# ESC-simple_V2A_ervinedit.net
KiCad netlist of a schematic drawn in EAGLE
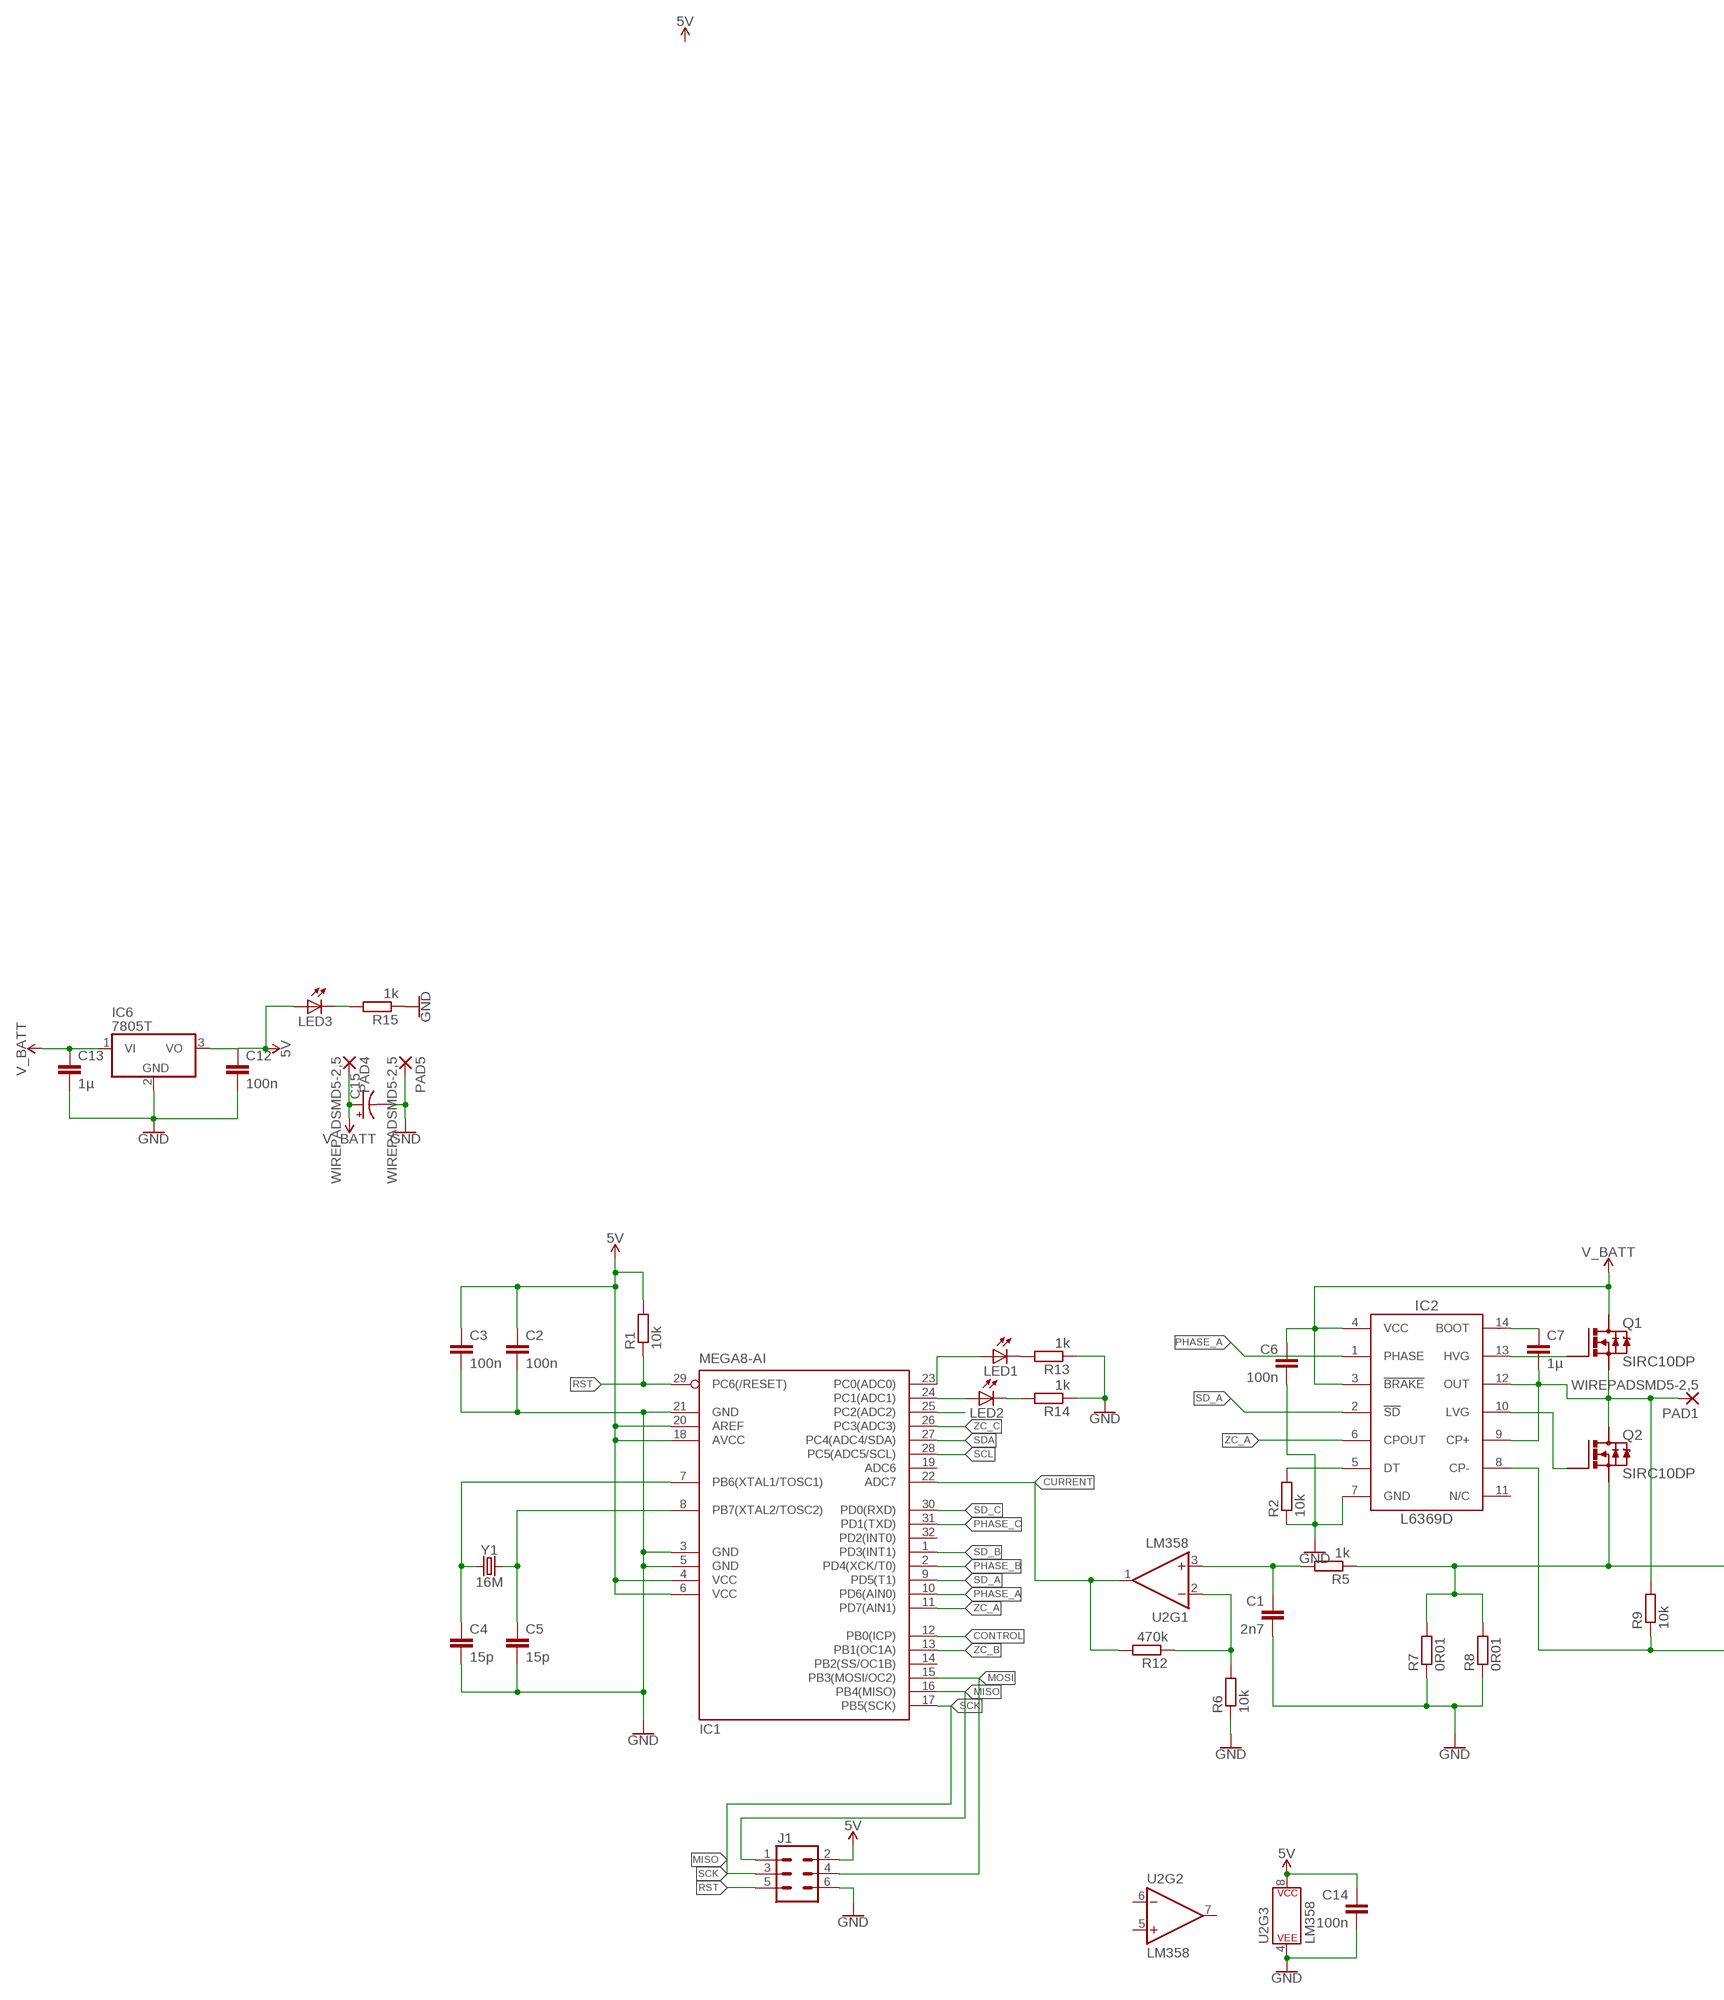
[diagram p0: schematic, sheet 1, part 1 of 2]
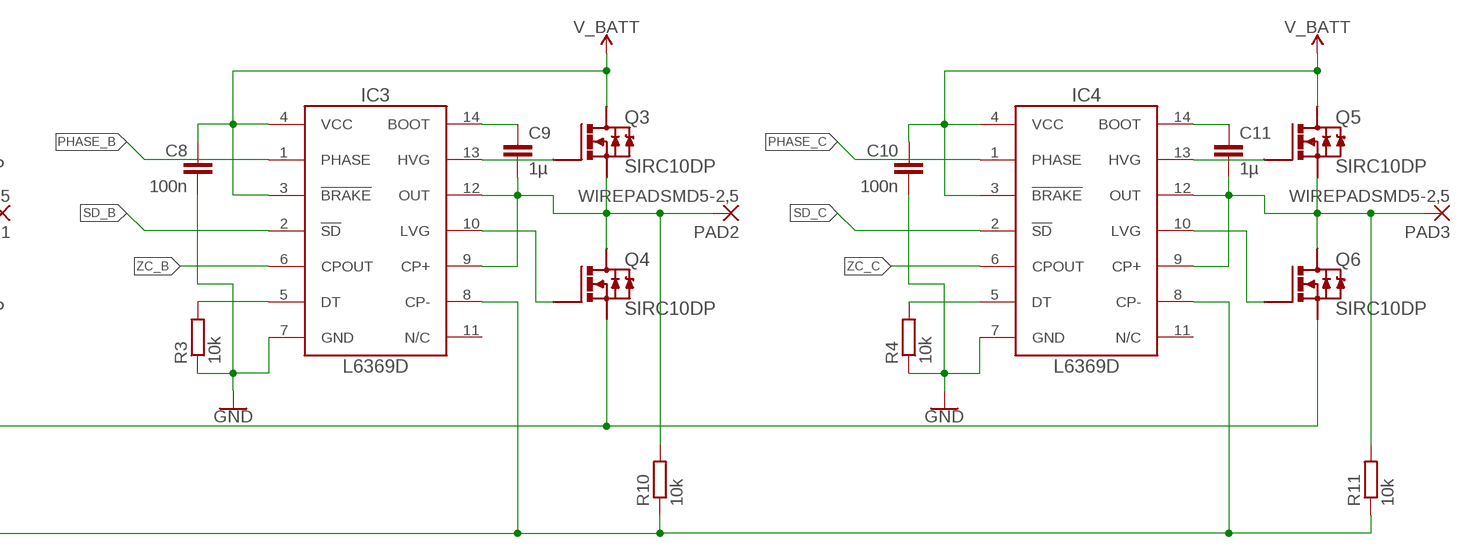
[diagram p1: schematic, sheet 1, part 2 of 2]

(export (version "E")
  (design (tool "Eeschema 10.0.6"))
  (components
    (comp (ref "C1")
      (value "2n7")
      (footprint "eagle-import:C1206K")
      (libsource (lib "eagle-import") (part "C-EUC1206K"))
    )
    (comp (ref "C2")
      (value "100n")
      (footprint "eagle-import:C1206K")
      (libsource (lib "eagle-import") (part "C-EUC1206K"))
    )
    (comp (ref "C3")
      (value "100n")
      (footprint "eagle-import:C1206K")
      (libsource (lib "eagle-import") (part "C-EUC1206K"))
    )
    (comp (ref "C4")
      (value "15p")
      (footprint "eagle-import:C1206K")
      (libsource (lib "eagle-import") (part "C-EUC1206K"))
    )
    (comp (ref "C5")
      (value "15p")
      (footprint "eagle-import:C1206K")
      (libsource (lib "eagle-import") (part "C-EUC1206K"))
    )
    (comp (ref "C6")
      (value "100n")
      (footprint "eagle-import:C1206K")
      (libsource (lib "eagle-import") (part "C-EUC1206K"))
    )
    (comp (ref "C7")
      (value "1µ")
      (footprint "eagle-import:C1206K")
      (libsource (lib "eagle-import") (part "C-EUC1206K"))
    )
    (comp (ref "C8")
      (value "100n")
      (footprint "eagle-import:C1206K")
      (libsource (lib "eagle-import") (part "C-EUC1206K"))
    )
    (comp (ref "C9")
      (value "1µ")
      (footprint "eagle-import:C1206K")
      (libsource (lib "eagle-import") (part "C-EUC1206K"))
    )
    (comp (ref "C10")
      (value "100n")
      (footprint "eagle-import:C1206K")
      (libsource (lib "eagle-import") (part "C-EUC1206K"))
    )
    (comp (ref "C11")
      (value "1µ")
      (footprint "eagle-import:C1206K")
      (libsource (lib "eagle-import") (part "C-EUC1206K"))
    )
    (comp (ref "C12")
      (value "100n")
      (footprint "eagle-import:C1206K")
      (libsource (lib "eagle-import") (part "C-EUC1206K"))
    )
    (comp (ref "C13")
      (value "1µ")
      (footprint "eagle-import:C1206K")
      (libsource (lib "eagle-import") (part "C-EUC1206K"))
    )
    (comp (ref "C14")
      (value "100n")
      (footprint "eagle-import:C1206K")
      (libsource (lib "eagle-import") (part "C-EUC1206K"))
    )
    (comp (ref "C15")
      (value "CPOL-USE5-13")
      (footprint "eagle-import:E5-13")
      (libsource (lib "eagle-import") (part "CPOL-USE5-13"))
    )
    (comp (ref "IC1")
      (value "MEGA8-AI")
      (footprint "eagle-import:TQFP32-08")
      (fields (field (name "MPN") "ATMEGA8-16AU"))
      (libsource (lib "eagle-import") (part "MEGA8-AI"))
    )
    (comp (ref "IC2")
      (value "L6369D")
      (footprint "eagle-import:SO-14")
      (libsource (lib "eagle-import") (part "L6369D"))
    )
    (comp (ref "IC3")
      (value "L6369D")
      (footprint "eagle-import:SO-14")
      (libsource (lib "eagle-import") (part "L6369D"))
    )
    (comp (ref "IC4")
      (value "L6369D")
      (footprint "eagle-import:SO-14")
      (libsource (lib "eagle-import") (part "L6369D"))
    )
    (comp (ref "IC6")
      (value "7805T")
      (footprint "eagle-import:TO220H")
      (libsource (lib "eagle-import") (part "78T05"))
    )
    (comp (ref "J1")
      (value "CONN_03X22X3_SILK_MALE_PTH")
      (footprint "eagle-import:2X3")
      (libsource (lib "eagle-import") (part "CONN_03X22X3_SILK_MALE_PTH"))
    )
    (comp (ref "LED1")
      (value "TLLR4400")
      (footprint "eagle-import:LED3MM")
      (fields (field (name "MF") "VISHAY SEMICONDUCTOR"))
      (libsource (lib "eagle-import") (part "TLLR4400"))
    )
    (comp (ref "LED2")
      (value "TLLR4400")
      (footprint "eagle-import:LED3MM")
      (fields (field (name "MF") "VISHAY SEMICONDUCTOR"))
      (libsource (lib "eagle-import") (part "TLLR4400"))
    )
    (comp (ref "LED3")
      (value "TLLR4400")
      (footprint "eagle-import:LED3MM")
      (fields (field (name "MF") "VISHAY SEMICONDUCTOR"))
      (libsource (lib "eagle-import") (part "TLLR4400"))
    )
    (comp (ref "PAD1")
      (value "WIREPADSMD5-2,5")
      (footprint "eagle-import:5-2,5")
      (libsource (lib "eagle-import") (part "WIREPADSMD5-2,5"))
    )
    (comp (ref "PAD2")
      (value "WIREPADSMD5-2,5")
      (footprint "eagle-import:5-2,5")
      (libsource (lib "eagle-import") (part "WIREPADSMD5-2,5"))
    )
    (comp (ref "PAD3")
      (value "WIREPADSMD5-2,5")
      (footprint "eagle-import:5-2,5")
      (libsource (lib "eagle-import") (part "WIREPADSMD5-2,5"))
    )
    (comp (ref "PAD4")
      (value "WIREPADSMD5-2,5")
      (footprint "eagle-import:5-2,5")
      (libsource (lib "eagle-import") (part "WIREPADSMD5-2,5"))
    )
    (comp (ref "PAD5")
      (value "WIREPADSMD5-2,5")
      (footprint "eagle-import:5-2,5")
      (libsource (lib "eagle-import") (part "WIREPADSMD5-2,5"))
    )
    (comp (ref "Q1")
      (value "SIRC10DP")
      (footprint "eagle-import:POWERPAK_SO-8_SINGLE")
      (libsource (lib "eagle-import") (part "SIRC10DP"))
    )
    (comp (ref "Q2")
      (value "SIRC10DP")
      (footprint "eagle-import:POWERPAK_SO-8_SINGLE")
      (libsource (lib "eagle-import") (part "SIRC10DP"))
    )
    (comp (ref "Q3")
      (value "SIRC10DP")
      (footprint "eagle-import:POWERPAK_SO-8_SINGLE")
      (libsource (lib "eagle-import") (part "SIRC10DP"))
    )
    (comp (ref "Q4")
      (value "SIRC10DP")
      (footprint "eagle-import:POWERPAK_SO-8_SINGLE")
      (libsource (lib "eagle-import") (part "SIRC10DP"))
    )
    (comp (ref "Q5")
      (value "SIRC10DP")
      (footprint "eagle-import:POWERPAK_SO-8_SINGLE")
      (libsource (lib "eagle-import") (part "SIRC10DP"))
    )
    (comp (ref "Q6")
      (value "SIRC10DP")
      (footprint "eagle-import:POWERPAK_SO-8_SINGLE")
      (libsource (lib "eagle-import") (part "SIRC10DP"))
    )
    (comp (ref "R1")
      (value "10k")
      (footprint "eagle-import:R1206")
      (libsource (lib "eagle-import") (part "R-EU_R1206"))
    )
    (comp (ref "R2")
      (value "10k")
      (footprint "eagle-import:R1206")
      (libsource (lib "eagle-import") (part "R-EU_R1206"))
    )
    (comp (ref "R3")
      (value "10k")
      (footprint "eagle-import:R1206")
      (libsource (lib "eagle-import") (part "R-EU_R1206"))
    )
    (comp (ref "R4")
      (value "10k")
      (footprint "eagle-import:R1206")
      (libsource (lib "eagle-import") (part "R-EU_R1206"))
    )
    (comp (ref "R5")
      (value "1k")
      (footprint "eagle-import:R1206")
      (libsource (lib "eagle-import") (part "R-EU_R1206"))
    )
    (comp (ref "R6")
      (value "10k")
      (footprint "eagle-import:R1206")
      (libsource (lib "eagle-import") (part "R-EU_R1206"))
    )
    (comp (ref "R7")
      (value "0R01")
      (footprint "eagle-import:R1206")
      (libsource (lib "eagle-import") (part "R-EU_R1206"))
    )
    (comp (ref "R8")
      (value "0R01")
      (footprint "eagle-import:R1206")
      (libsource (lib "eagle-import") (part "R-EU_R1206"))
    )
    (comp (ref "R9")
      (value "10k")
      (footprint "eagle-import:R1206")
      (libsource (lib "eagle-import") (part "R-EU_R1206"))
    )
    (comp (ref "R10")
      (value "10k")
      (footprint "eagle-import:R1206")
      (libsource (lib "eagle-import") (part "R-EU_R1206"))
    )
    (comp (ref "R11")
      (value "10k")
      (footprint "eagle-import:R1206")
      (libsource (lib "eagle-import") (part "R-EU_R1206"))
    )
    (comp (ref "R12")
      (value "470k")
      (footprint "eagle-import:R1206")
      (libsource (lib "eagle-import") (part "R-EU_R1206"))
    )
    (comp (ref "R13")
      (value "1k")
      (footprint "eagle-import:R1206")
      (libsource (lib "eagle-import") (part "R-EU_R1206"))
    )
    (comp (ref "R14")
      (value "1k")
      (footprint "eagle-import:R1206")
      (libsource (lib "eagle-import") (part "R-EU_R1206"))
    )
    (comp (ref "R15")
      (value "1k")
      (footprint "eagle-import:R1206")
      (libsource (lib "eagle-import") (part "R-EU_R1206"))
    )
    (comp (ref "U2")
      (value "LM358")
      (footprint "eagle-import:DIP08")
      (libsource (lib "eagle-import") (part "LM358"))
    )
    (comp (ref "Y1")
      (value "16M")
      (footprint "eagle-import:HC49UP")
      (libsource (lib "eagle-import") (part "CRYSTALSMD-HC49UP"))
    )
  )
  (nets
    (net (code "1") (name "5V") (class "Default")
      (node (ref "C12") (pin "1") (pinfunction "1_1") (pintype "passive"))
      (node (ref "C14") (pin "1") (pinfunction "1_1") (pintype "passive"))
      (node (ref "C2") (pin "1") (pinfunction "1_1") (pintype "passive"))
      (node (ref "C3") (pin "1") (pinfunction "1_1") (pintype "passive"))
      (node (ref "IC1") (pin "18") (pinfunction "AVCC_18") (pintype "power_in"))
      (node (ref "IC1") (pin "20") (pinfunction "AREF_20") (pintype "passive"))
      (node (ref "IC1") (pin "4") (pinfunction "VCC_4") (pintype "power_in"))
      (node (ref "IC1") (pin "6") (pinfunction "VCC_6") (pintype "power_in"))
      (node (ref "IC6") (pin "3") (pinfunction "VO_3") (pintype "passive"))
      (node (ref "J1") (pin "2") (pinfunction "2_2") (pintype "bidirectional"))
      (node (ref "LED3") (pin "A") (pinfunction "A_A") (pintype "passive"))
      (node (ref "R1") (pin "2") (pinfunction "2_2") (pintype "passive"))
      (node (ref "U2") (pin "8") (pinfunction "P$V+_8") (pintype "bidirectional"))
    )
    (net (code "2") (name "CONTROL") (class "Default")
      (node (ref "IC1") (pin "12") (pinfunction "PB0(ICP)_12") (pintype "bidirectional"))
    )
    (net (code "3") (name "CURRENT") (class "Default")
      (node (ref "IC1") (pin "22") (pinfunction "ADC7_22") (pintype "bidirectional"))
      (node (ref "R12") (pin "2") (pinfunction "2_2") (pintype "passive"))
      (node (ref "U2") (pin "1") (pinfunction "OUT_1") (pintype "output"))
    )
    (net (code "4") (name "GND") (class "Default")
      (node (ref "C1") (pin "2") (pinfunction "2_2") (pintype "passive"))
      (node (ref "C10") (pin "2") (pinfunction "2_2") (pintype "passive"))
      (node (ref "C12") (pin "2") (pinfunction "2_2") (pintype "passive"))
      (node (ref "C13") (pin "2") (pinfunction "2_2") (pintype "passive"))
      (node (ref "C14") (pin "2") (pinfunction "2_2") (pintype "passive"))
      (node (ref "C15") (pin "-") (pinfunction "-_-") (pintype "passive"))
      (node (ref "C2") (pin "2") (pinfunction "2_2") (pintype "passive"))
      (node (ref "C3") (pin "2") (pinfunction "2_2") (pintype "passive"))
      (node (ref "C4") (pin "2") (pinfunction "2_2") (pintype "passive"))
      (node (ref "C5") (pin "2") (pinfunction "2_2") (pintype "passive"))
      (node (ref "C6") (pin "2") (pinfunction "2_2") (pintype "passive"))
      (node (ref "C8") (pin "2") (pinfunction "2_2") (pintype "passive"))
      (node (ref "IC1") (pin "21") (pinfunction "GND_21") (pintype "power_in"))
      (node (ref "IC1") (pin "3") (pinfunction "GND_3") (pintype "power_in"))
      (node (ref "IC1") (pin "5") (pinfunction "GND_5") (pintype "power_in"))
      (node (ref "IC2") (pin "7") (pinfunction "GND_7") (pintype "power_in"))
      (node (ref "IC3") (pin "7") (pinfunction "GND_7") (pintype "power_in"))
      (node (ref "IC4") (pin "7") (pinfunction "GND_7") (pintype "power_in"))
      (node (ref "IC6") (pin "2") (pinfunction "GND_2") (pintype "passive"))
      (node (ref "J1") (pin "6") (pinfunction "6_6") (pintype "bidirectional"))
      (node (ref "PAD5") (pin "1") (pinfunction "P_1") (pintype "passive"))
      (node (ref "R13") (pin "1") (pinfunction "1_1") (pintype "passive"))
      (node (ref "R14") (pin "1") (pinfunction "1_1") (pintype "passive"))
      (node (ref "R15") (pin "1") (pinfunction "1_1") (pintype "passive"))
      (node (ref "R2") (pin "1") (pinfunction "1_1") (pintype "passive"))
      (node (ref "R3") (pin "1") (pinfunction "1_1") (pintype "passive"))
      (node (ref "R4") (pin "1") (pinfunction "1_1") (pintype "passive"))
      (node (ref "R6") (pin "1") (pinfunction "1_1") (pintype "passive"))
      (node (ref "R7") (pin "1") (pinfunction "1_1") (pintype "passive"))
      (node (ref "R8") (pin "1") (pinfunction "1_1") (pintype "passive"))
      (node (ref "U2") (pin "4") (pinfunction "P$V-_4") (pintype "bidirectional"))
    )
    (net (code "5") (name "MISO") (class "Default")
      (node (ref "IC1") (pin "16") (pinfunction "PB4(MISO)_16") (pintype "bidirectional"))
      (node (ref "J1") (pin "1") (pinfunction "1_1") (pintype "bidirectional"))
    )
    (net (code "6") (name "MOSI") (class "Default")
      (node (ref "IC1") (pin "15") (pinfunction "PB3(MOSI/OC2)_15") (pintype "bidirectional"))
      (node (ref "J1") (pin "4") (pinfunction "4_4") (pintype "bidirectional"))
    )
    (net (code "7") (name "Net-(IC1-PB6(XTAL1{slash}TOSC1))") (class "Default")
      (node (ref "C4") (pin "1") (pinfunction "1_1") (pintype "passive"))
      (node (ref "IC1") (pin "7") (pinfunction "PB6(XTAL1/TOSC1)_7") (pintype "bidirectional"))
      (node (ref "Y1") (pin "1") (pinfunction "1_1") (pintype "passive"))
    )
    (net (code "8") (name "Net-(IC1-PB7(XTAL2{slash}TOSC2))") (class "Default")
      (node (ref "C5") (pin "1") (pinfunction "1_1") (pintype "passive"))
      (node (ref "IC1") (pin "8") (pinfunction "PB7(XTAL2/TOSC2)_8") (pintype "bidirectional"))
      (node (ref "Y1") (pin "2") (pinfunction "2_2") (pintype "passive"))
    )
    (net (code "9") (name "Net-(IC1-PC0(ADC0))") (class "Default")
      (node (ref "IC1") (pin "23") (pinfunction "PC0(ADC0)_23") (pintype "bidirectional"))
      (node (ref "LED1") (pin "A") (pinfunction "A_A") (pintype "passive"))
    )
    (net (code "10") (name "Net-(IC1-PC1(ADC1))") (class "Default")
      (node (ref "IC1") (pin "24") (pinfunction "PC1(ADC1)_24") (pintype "bidirectional"))
      (node (ref "LED2") (pin "A") (pinfunction "A_A") (pintype "passive"))
    )
    (net (code "11") (name "Net-(IC2-BOOT)") (class "Default")
      (node (ref "C7") (pin "1") (pinfunction "1_1") (pintype "passive"))
      (node (ref "IC2") (pin "14") (pinfunction "BOOT_14") (pintype "power_in"))
    )
    (net (code "12") (name "Net-(IC2-CP+)") (class "Default")
      (node (ref "C7") (pin "2") (pinfunction "2_2") (pintype "passive"))
      (node (ref "IC2") (pin "12") (pinfunction "OUT_12") (pintype "output"))
      (node (ref "IC2") (pin "9") (pinfunction "CP+_9") (pintype "input"))
      (node (ref "PAD1") (pin "1") (pinfunction "P_1") (pintype "passive"))
      (node (ref "Q1") (pin "1") (pinfunction "S_1") (pintype "bidirectional"))
      (node (ref "Q1") (pin "2") (pinfunction "S_2") (pintype "bidirectional"))
      (node (ref "Q1") (pin "3") (pinfunction "S_3") (pintype "bidirectional"))
      (node (ref "Q2") (pin "5") (pinfunction "D_5") (pintype "bidirectional"))
      (node (ref "Q2") (pin "6") (pinfunction "D_6") (pintype "bidirectional"))
      (node (ref "Q2") (pin "7") (pinfunction "D_7") (pintype "bidirectional"))
      (node (ref "Q2") (pin "8") (pinfunction "D_8") (pintype "bidirectional"))
      (node (ref "Q2") (pin "9") (pinfunction "D_9") (pintype "bidirectional"))
      (node (ref "R9") (pin "2") (pinfunction "2_2") (pintype "passive"))
    )
    (net (code "13") (name "Net-(IC2-CP-)") (class "Default")
      (node (ref "IC2") (pin "8") (pinfunction "CP-_8") (pintype "input"))
      (node (ref "IC3") (pin "8") (pinfunction "CP-_8") (pintype "input"))
      (node (ref "IC4") (pin "8") (pinfunction "CP-_8") (pintype "input"))
      (node (ref "R10") (pin "1") (pinfunction "1_1") (pintype "passive"))
      (node (ref "R11") (pin "1") (pinfunction "1_1") (pintype "passive"))
      (node (ref "R9") (pin "1") (pinfunction "1_1") (pintype "passive"))
    )
    (net (code "14") (name "Net-(IC2-DT)") (class "Default")
      (node (ref "IC2") (pin "5") (pinfunction "DT_5") (pintype "input"))
      (node (ref "R2") (pin "2") (pinfunction "2_2") (pintype "passive"))
    )
    (net (code "15") (name "Net-(IC2-HVG)") (class "Default")
      (node (ref "IC2") (pin "13") (pinfunction "HVG_13") (pintype "output"))
      (node (ref "Q1") (pin "4") (pinfunction "G_4") (pintype "bidirectional"))
    )
    (net (code "16") (name "Net-(IC2-LVG)") (class "Default")
      (node (ref "IC2") (pin "10") (pinfunction "LVG_10") (pintype "output"))
      (node (ref "Q2") (pin "4") (pinfunction "G_4") (pintype "bidirectional"))
    )
    (net (code "17") (name "Net-(IC3-BOOT)") (class "Default")
      (node (ref "C9") (pin "1") (pinfunction "1_1") (pintype "passive"))
      (node (ref "IC3") (pin "14") (pinfunction "BOOT_14") (pintype "power_in"))
    )
    (net (code "18") (name "Net-(IC3-CP+)") (class "Default")
      (node (ref "C9") (pin "2") (pinfunction "2_2") (pintype "passive"))
      (node (ref "IC3") (pin "12") (pinfunction "OUT_12") (pintype "output"))
      (node (ref "IC3") (pin "9") (pinfunction "CP+_9") (pintype "input"))
      (node (ref "PAD2") (pin "1") (pinfunction "P_1") (pintype "passive"))
      (node (ref "Q3") (pin "1") (pinfunction "S_1") (pintype "bidirectional"))
      (node (ref "Q3") (pin "2") (pinfunction "S_2") (pintype "bidirectional"))
      (node (ref "Q3") (pin "3") (pinfunction "S_3") (pintype "bidirectional"))
      (node (ref "Q4") (pin "5") (pinfunction "D_5") (pintype "bidirectional"))
      (node (ref "Q4") (pin "6") (pinfunction "D_6") (pintype "bidirectional"))
      (node (ref "Q4") (pin "7") (pinfunction "D_7") (pintype "bidirectional"))
      (node (ref "Q4") (pin "8") (pinfunction "D_8") (pintype "bidirectional"))
      (node (ref "Q4") (pin "9") (pinfunction "D_9") (pintype "bidirectional"))
      (node (ref "R10") (pin "2") (pinfunction "2_2") (pintype "passive"))
    )
    (net (code "19") (name "Net-(IC3-DT)") (class "Default")
      (node (ref "IC3") (pin "5") (pinfunction "DT_5") (pintype "input"))
      (node (ref "R3") (pin "2") (pinfunction "2_2") (pintype "passive"))
    )
    (net (code "20") (name "Net-(IC3-HVG)") (class "Default")
      (node (ref "IC3") (pin "13") (pinfunction "HVG_13") (pintype "output"))
      (node (ref "Q3") (pin "4") (pinfunction "G_4") (pintype "bidirectional"))
    )
    (net (code "21") (name "Net-(IC3-LVG)") (class "Default")
      (node (ref "IC3") (pin "10") (pinfunction "LVG_10") (pintype "output"))
      (node (ref "Q4") (pin "4") (pinfunction "G_4") (pintype "bidirectional"))
    )
    (net (code "22") (name "Net-(IC4-BOOT)") (class "Default")
      (node (ref "C11") (pin "1") (pinfunction "1_1") (pintype "passive"))
      (node (ref "IC4") (pin "14") (pinfunction "BOOT_14") (pintype "power_in"))
    )
    (net (code "23") (name "Net-(IC4-CP+)") (class "Default")
      (node (ref "C11") (pin "2") (pinfunction "2_2") (pintype "passive"))
      (node (ref "IC4") (pin "12") (pinfunction "OUT_12") (pintype "output"))
      (node (ref "IC4") (pin "9") (pinfunction "CP+_9") (pintype "input"))
      (node (ref "PAD3") (pin "1") (pinfunction "P_1") (pintype "passive"))
      (node (ref "Q5") (pin "1") (pinfunction "S_1") (pintype "bidirectional"))
      (node (ref "Q5") (pin "2") (pinfunction "S_2") (pintype "bidirectional"))
      (node (ref "Q5") (pin "3") (pinfunction "S_3") (pintype "bidirectional"))
      (node (ref "Q6") (pin "5") (pinfunction "D_5") (pintype "bidirectional"))
      (node (ref "Q6") (pin "6") (pinfunction "D_6") (pintype "bidirectional"))
      (node (ref "Q6") (pin "7") (pinfunction "D_7") (pintype "bidirectional"))
      (node (ref "Q6") (pin "8") (pinfunction "D_8") (pintype "bidirectional"))
      (node (ref "Q6") (pin "9") (pinfunction "D_9") (pintype "bidirectional"))
      (node (ref "R11") (pin "2") (pinfunction "2_2") (pintype "passive"))
    )
    (net (code "24") (name "Net-(IC4-DT)") (class "Default")
      (node (ref "IC4") (pin "5") (pinfunction "DT_5") (pintype "input"))
      (node (ref "R4") (pin "2") (pinfunction "2_2") (pintype "passive"))
    )
    (net (code "25") (name "Net-(IC4-HVG)") (class "Default")
      (node (ref "IC4") (pin "13") (pinfunction "HVG_13") (pintype "output"))
      (node (ref "Q5") (pin "4") (pinfunction "G_4") (pintype "bidirectional"))
    )
    (net (code "26") (name "Net-(IC4-LVG)") (class "Default")
      (node (ref "IC4") (pin "10") (pinfunction "LVG_10") (pintype "output"))
      (node (ref "Q6") (pin "4") (pinfunction "G_4") (pintype "bidirectional"))
    )
    (net (code "27") (name "Net-(LED1-C)") (class "Default")
      (node (ref "LED1") (pin "K") (pinfunction "C_K") (pintype "passive"))
      (node (ref "R13") (pin "2") (pinfunction "2_2") (pintype "passive"))
    )
    (net (code "28") (name "Net-(LED2-C)") (class "Default")
      (node (ref "LED2") (pin "K") (pinfunction "C_K") (pintype "passive"))
      (node (ref "R14") (pin "2") (pinfunction "2_2") (pintype "passive"))
    )
    (net (code "29") (name "Net-(LED3-C)") (class "Default")
      (node (ref "LED3") (pin "K") (pinfunction "C_K") (pintype "passive"))
      (node (ref "R15") (pin "2") (pinfunction "2_2") (pintype "passive"))
    )
    (net (code "30") (name "Net-(Q2-S-Pad1)") (class "Default")
      (node (ref "Q2") (pin "1") (pinfunction "S_1") (pintype "bidirectional"))
      (node (ref "Q2") (pin "2") (pinfunction "S_2") (pintype "bidirectional"))
      (node (ref "Q2") (pin "3") (pinfunction "S_3") (pintype "bidirectional"))
      (node (ref "Q4") (pin "1") (pinfunction "S_1") (pintype "bidirectional"))
      (node (ref "Q4") (pin "2") (pinfunction "S_2") (pintype "bidirectional"))
      (node (ref "Q4") (pin "3") (pinfunction "S_3") (pintype "bidirectional"))
      (node (ref "Q6") (pin "1") (pinfunction "S_1") (pintype "bidirectional"))
      (node (ref "Q6") (pin "2") (pinfunction "S_2") (pintype "bidirectional"))
      (node (ref "Q6") (pin "3") (pinfunction "S_3") (pintype "bidirectional"))
      (node (ref "R5") (pin "1") (pinfunction "1_1") (pintype "passive"))
      (node (ref "R7") (pin "2") (pinfunction "2_2") (pintype "passive"))
      (node (ref "R8") (pin "2") (pinfunction "2_2") (pintype "passive"))
    )
    (net (code "31") (name "Net-(U2A-+IN)") (class "Default")
      (node (ref "C1") (pin "1") (pinfunction "1_1") (pintype "passive"))
      (node (ref "R5") (pin "2") (pinfunction "2_2") (pintype "passive"))
      (node (ref "U2") (pin "3") (pinfunction "+IN_3") (pintype "input"))
    )
    (net (code "32") (name "Net-(U2A--IN)") (class "Default")
      (node (ref "R12") (pin "1") (pinfunction "1_1") (pintype "passive"))
      (node (ref "R6") (pin "2") (pinfunction "2_2") (pintype "passive"))
      (node (ref "U2") (pin "2") (pinfunction "-IN_2") (pintype "input"))
    )
    (net (code "33") (name "PHASE_A") (class "Default")
      (node (ref "IC1") (pin "10") (pinfunction "PD6(AIN0)_10") (pintype "bidirectional"))
      (node (ref "IC2") (pin "1") (pinfunction "PHASE_1") (pintype "input"))
    )
    (net (code "34") (name "PHASE_B") (class "Default")
      (node (ref "IC1") (pin "2") (pinfunction "PD4(XCK/T0)_2") (pintype "bidirectional"))
      (node (ref "IC3") (pin "1") (pinfunction "PHASE_1") (pintype "input"))
    )
    (net (code "35") (name "PHASE_C") (class "Default")
      (node (ref "IC1") (pin "31") (pinfunction "PD1(TXD)_31") (pintype "bidirectional"))
      (node (ref "IC4") (pin "1") (pinfunction "PHASE_1") (pintype "input"))
    )
    (net (code "36") (name "RST") (class "Default")
      (node (ref "IC1") (pin "29") (pinfunction "PC6(/RESET)_29") (pintype "bidirectional"))
      (node (ref "J1") (pin "5") (pinfunction "5_5") (pintype "bidirectional"))
      (node (ref "R1") (pin "1") (pinfunction "1_1") (pintype "passive"))
    )
    (net (code "37") (name "SCK") (class "Default")
      (node (ref "IC1") (pin "17") (pinfunction "PB5(SCK)_17") (pintype "bidirectional"))
      (node (ref "J1") (pin "3") (pinfunction "3_3") (pintype "bidirectional"))
    )
    (net (code "38") (name "SCL") (class "Default")
      (node (ref "IC1") (pin "28") (pinfunction "PC5(ADC5/SCL)_28") (pintype "bidirectional"))
    )
    (net (code "39") (name "SDA") (class "Default")
      (node (ref "IC1") (pin "27") (pinfunction "PC4(ADC4/SDA)_27") (pintype "bidirectional"))
    )
    (net (code "40") (name "SD_A") (class "Default")
      (node (ref "IC1") (pin "9") (pinfunction "PD5(T1)_9") (pintype "bidirectional"))
      (node (ref "IC2") (pin "2") (pinfunction "~{SD}_2") (pintype "input"))
    )
    (net (code "41") (name "SD_B") (class "Default")
      (node (ref "IC1") (pin "1") (pinfunction "PD3(INT1)_1") (pintype "bidirectional"))
      (node (ref "IC3") (pin "2") (pinfunction "~{SD}_2") (pintype "input"))
    )
    (net (code "42") (name "SD_C") (class "Default")
      (node (ref "IC1") (pin "30") (pinfunction "PD0(RXD)_30") (pintype "bidirectional"))
      (node (ref "IC4") (pin "2") (pinfunction "~{SD}_2") (pintype "input"))
    )
    (net (code "43") (name "V_BATT") (class "Default")
      (node (ref "C10") (pin "1") (pinfunction "1_1") (pintype "passive"))
      (node (ref "C13") (pin "1") (pinfunction "1_1") (pintype "passive"))
      (node (ref "C15") (pin "+") (pinfunction "+_+") (pintype "passive"))
      (node (ref "C6") (pin "1") (pinfunction "1_1") (pintype "passive"))
      (node (ref "C8") (pin "1") (pinfunction "1_1") (pintype "passive"))
      (node (ref "IC2") (pin "3") (pinfunction "~{BRAKE}_3") (pintype "input"))
      (node (ref "IC2") (pin "4") (pinfunction "VCC_4") (pintype "power_in"))
      (node (ref "IC3") (pin "3") (pinfunction "~{BRAKE}_3") (pintype "input"))
      (node (ref "IC3") (pin "4") (pinfunction "VCC_4") (pintype "power_in"))
      (node (ref "IC4") (pin "3") (pinfunction "~{BRAKE}_3") (pintype "input"))
      (node (ref "IC4") (pin "4") (pinfunction "VCC_4") (pintype "power_in"))
      (node (ref "IC6") (pin "1") (pinfunction "VI_1") (pintype "input"))
      (node (ref "PAD4") (pin "1") (pinfunction "P_1") (pintype "passive"))
      (node (ref "Q1") (pin "5") (pinfunction "D_5") (pintype "bidirectional"))
      (node (ref "Q1") (pin "6") (pinfunction "D_6") (pintype "bidirectional"))
      (node (ref "Q1") (pin "7") (pinfunction "D_7") (pintype "bidirectional"))
      (node (ref "Q1") (pin "8") (pinfunction "D_8") (pintype "bidirectional"))
      (node (ref "Q1") (pin "9") (pinfunction "D_9") (pintype "bidirectional"))
      (node (ref "Q3") (pin "5") (pinfunction "D_5") (pintype "bidirectional"))
      (node (ref "Q3") (pin "6") (pinfunction "D_6") (pintype "bidirectional"))
      (node (ref "Q3") (pin "7") (pinfunction "D_7") (pintype "bidirectional"))
      (node (ref "Q3") (pin "8") (pinfunction "D_8") (pintype "bidirectional"))
      (node (ref "Q3") (pin "9") (pinfunction "D_9") (pintype "bidirectional"))
      (node (ref "Q5") (pin "5") (pinfunction "D_5") (pintype "bidirectional"))
      (node (ref "Q5") (pin "6") (pinfunction "D_6") (pintype "bidirectional"))
      (node (ref "Q5") (pin "7") (pinfunction "D_7") (pintype "bidirectional"))
      (node (ref "Q5") (pin "8") (pinfunction "D_8") (pintype "bidirectional"))
      (node (ref "Q5") (pin "9") (pinfunction "D_9") (pintype "bidirectional"))
    )
    (net (code "44") (name "ZC_A") (class "Default")
      (node (ref "IC1") (pin "11") (pinfunction "PD7(AIN1)_11") (pintype "bidirectional"))
      (node (ref "IC2") (pin "6") (pinfunction "CPOUT_6") (pintype "output"))
    )
    (net (code "45") (name "ZC_B") (class "Default")
      (node (ref "IC1") (pin "13") (pinfunction "PB1(OC1A)_13") (pintype "bidirectional"))
      (node (ref "IC3") (pin "6") (pinfunction "CPOUT_6") (pintype "output"))
    )
    (net (code "46") (name "ZC_C") (class "Default")
      (node (ref "IC1") (pin "26") (pinfunction "PC3(ADC3)_26") (pintype "bidirectional"))
      (node (ref "IC4") (pin "6") (pinfunction "CPOUT_6") (pintype "output"))
    )
    (net (code "47") (name "unconnected-(IC1-ADC6-Pad19)") (class "Default")
      (node (ref "IC1") (pin "19") (pinfunction "ADC6_19") (pintype "bidirectional"))
    )
    (net (code "48") (name "unconnected-(IC1-PB2(SS{slash}OC1B)-Pad14)") (class "Default")
      (node (ref "IC1") (pin "14") (pinfunction "PB2(SS/OC1B)_14") (pintype "bidirectional"))
    )
    (net (code "49") (name "unconnected-(IC1-PC2(ADC2)-Pad25)") (class "Default")
      (node (ref "IC1") (pin "25") (pinfunction "PC2(ADC2)_25") (pintype "bidirectional"))
    )
    (net (code "50") (name "unconnected-(IC1-PD2(INT0)-Pad32)") (class "Default")
      (node (ref "IC1") (pin "32") (pinfunction "PD2(INT0)_32") (pintype "bidirectional"))
    )
    (net (code "51") (name "unconnected-(IC2-N{slash}C-Pad11)") (class "Default")
      (node (ref "IC2") (pin "11") (pinfunction "N/C_11") (pintype "no_connect"))
    )
    (net (code "52") (name "unconnected-(IC3-N{slash}C-Pad11)") (class "Default")
      (node (ref "IC3") (pin "11") (pinfunction "N/C_11") (pintype "no_connect"))
    )
    (net (code "53") (name "unconnected-(IC4-N{slash}C-Pad11)") (class "Default")
      (node (ref "IC4") (pin "11") (pinfunction "N/C_11") (pintype "no_connect"))
    )
    (net (code "54") (name "unconnected-(U2B-+IN-Pad5)") (class "Default")
      (node (ref "U2") (pin "5") (pinfunction "+IN_5") (pintype "input"))
    )
    (net (code "55") (name "unconnected-(U2B--IN-Pad6)") (class "Default")
      (node (ref "U2") (pin "6") (pinfunction "-IN_6") (pintype "input"))
    )
    (net (code "56") (name "unconnected-(U2B-OUT-Pad7)") (class "Default")
      (node (ref "U2") (pin "7") (pinfunction "OUT_7") (pintype "output"))
    )
  )
)
